# PWS.net
KiCad netlist of a schematic drawn in EAGLE
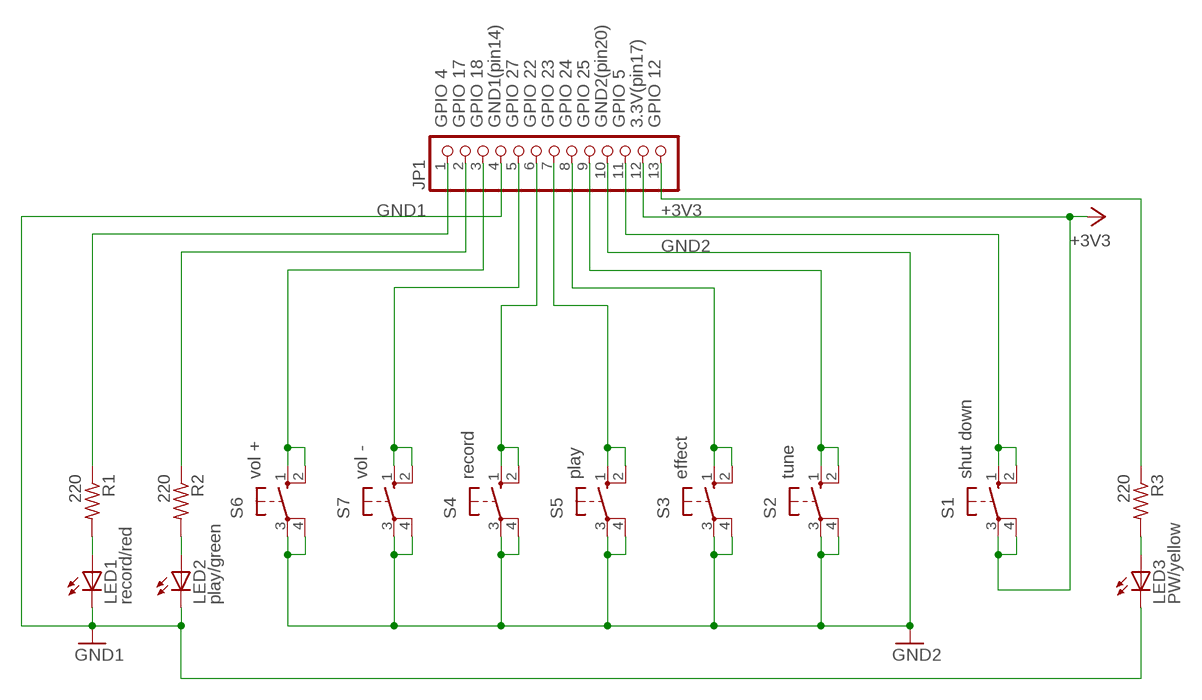
[diagram p0: schematic, sheet 1]

(export (version "E")
  (design (tool "Eeschema 10.0.6"))
  (components
    (comp (ref "JP1")
      (value "PINHD-1X13")
      (footprint "eagle-import:1X13")
      (libsource (lib "eagle-import") (part "PINHD-1X13"))
    )
    (comp (ref "LED1")
      (value "record/red")
      (footprint "eagle-import:LED3MM")
      (libsource (lib "eagle-import") (part "LED3MM"))
    )
    (comp (ref "LED2")
      (value "play/green")
      (footprint "eagle-import:LED3MM")
      (libsource (lib "eagle-import") (part "LED3MM"))
    )
    (comp (ref "LED3")
      (value "PW/yellow")
      (footprint "eagle-import:LED3MM")
      (libsource (lib "eagle-import") (part "LED3MM"))
    )
    (comp (ref "R1")
      (value "220")
      (footprint "eagle-import:0204_5")
      (libsource (lib "eagle-import") (part "R-US_0204/5"))
    )
    (comp (ref "R2")
      (value "220")
      (footprint "eagle-import:0204_5")
      (libsource (lib "eagle-import") (part "R-US_0204/5"))
    )
    (comp (ref "R3")
      (value "220")
      (footprint "eagle-import:0204_5")
      (libsource (lib "eagle-import") (part "R-US_0204/5"))
    )
    (comp (ref "S1")
      (value "shut down")
      (footprint "eagle-import:B3F-10XX")
      (fields (field (name "MPN") "B3F-1000"))
      (libsource (lib "eagle-import") (part "10-XX"))
    )
    (comp (ref "S2")
      (value "tune")
      (footprint "eagle-import:B3F-10XX")
      (fields (field (name "MPN") "B3F-1000"))
      (libsource (lib "eagle-import") (part "10-XX"))
    )
    (comp (ref "S3")
      (value "effect")
      (footprint "eagle-import:B3F-10XX")
      (fields (field (name "MPN") "B3F-1000"))
      (libsource (lib "eagle-import") (part "10-XX"))
    )
    (comp (ref "S4")
      (value "record")
      (footprint "eagle-import:B3F-10XX")
      (fields (field (name "MPN") "B3F-1000"))
      (libsource (lib "eagle-import") (part "10-XX"))
    )
    (comp (ref "S5")
      (value "play")
      (footprint "eagle-import:B3F-10XX")
      (fields (field (name "MPN") "B3F-1000"))
      (libsource (lib "eagle-import") (part "10-XX"))
    )
    (comp (ref "S6")
      (value "vol +")
      (footprint "eagle-import:B3F-10XX")
      (fields (field (name "MPN") "B3F-1000"))
      (libsource (lib "eagle-import") (part "10-XX"))
    )
    (comp (ref "S7")
      (value "vol -")
      (footprint "eagle-import:B3F-10XX")
      (fields (field (name "MPN") "B3F-1000"))
      (libsource (lib "eagle-import") (part "10-XX"))
    )
  )
  (nets
    (net (code "1") (name "+3V3") (class "Default")
      (node (ref "JP1") (pin "12") (pinfunction "12_12") (pintype "passive"))
      (node (ref "S1") (pin "3") (pinfunction "P_3") (pintype "passive"))
      (node (ref "S1") (pin "4") (pinfunction "P1_4") (pintype "passive"))
    )
    (net (code "2") (name "GND1") (class "Default")
      (node (ref "JP1") (pin "4") (pinfunction "4_4") (pintype "passive"))
      (node (ref "LED1") (pin "K") (pinfunction "C_K") (pintype "passive"))
      (node (ref "LED2") (pin "K") (pinfunction "C_K") (pintype "passive"))
      (node (ref "LED3") (pin "K") (pinfunction "C_K") (pintype "passive"))
    )
    (net (code "3") (name "GND2") (class "Default")
      (node (ref "JP1") (pin "10") (pinfunction "10_10") (pintype "passive"))
      (node (ref "S2") (pin "3") (pinfunction "P_3") (pintype "passive"))
      (node (ref "S2") (pin "4") (pinfunction "P1_4") (pintype "passive"))
      (node (ref "S3") (pin "3") (pinfunction "P_3") (pintype "passive"))
      (node (ref "S3") (pin "4") (pinfunction "P1_4") (pintype "passive"))
      (node (ref "S4") (pin "3") (pinfunction "P_3") (pintype "passive"))
      (node (ref "S4") (pin "4") (pinfunction "P1_4") (pintype "passive"))
      (node (ref "S5") (pin "3") (pinfunction "P_3") (pintype "passive"))
      (node (ref "S5") (pin "4") (pinfunction "P1_4") (pintype "passive"))
      (node (ref "S6") (pin "3") (pinfunction "P_3") (pintype "passive"))
      (node (ref "S6") (pin "4") (pinfunction "P1_4") (pintype "passive"))
      (node (ref "S7") (pin "3") (pinfunction "P_3") (pintype "passive"))
      (node (ref "S7") (pin "4") (pinfunction "P1_4") (pintype "passive"))
    )
    (net (code "4") (name "Net-(JP1-Pad1)") (class "Default")
      (node (ref "JP1") (pin "1") (pinfunction "1_1") (pintype "passive"))
      (node (ref "R1") (pin "1") (pinfunction "1_1") (pintype "passive"))
    )
    (net (code "5") (name "Net-(JP1-Pad2)") (class "Default")
      (node (ref "JP1") (pin "2") (pinfunction "2_2") (pintype "passive"))
      (node (ref "R2") (pin "1") (pinfunction "1_1") (pintype "passive"))
    )
    (net (code "6") (name "Net-(JP1-Pad13)") (class "Default")
      (node (ref "JP1") (pin "13") (pinfunction "13_13") (pintype "passive"))
      (node (ref "R3") (pin "1") (pinfunction "1_1") (pintype "passive"))
    )
    (net (code "7") (name "Net-(LED1-PadA)") (class "Default")
      (node (ref "LED1") (pin "A") (pinfunction "A_A") (pintype "passive"))
      (node (ref "R1") (pin "2") (pinfunction "2_2") (pintype "passive"))
    )
    (net (code "8") (name "Net-(LED2-PadA)") (class "Default")
      (node (ref "LED2") (pin "A") (pinfunction "A_A") (pintype "passive"))
      (node (ref "R2") (pin "2") (pinfunction "2_2") (pintype "passive"))
    )
    (net (code "9") (name "Net-(LED3-PadA)") (class "Default")
      (node (ref "LED3") (pin "A") (pinfunction "A_A") (pintype "passive"))
      (node (ref "R3") (pin "2") (pinfunction "2_2") (pintype "passive"))
    )
    (net (code "10") (name "Net-(S1-S)") (class "Default")
      (node (ref "JP1") (pin "11") (pinfunction "11_11") (pintype "passive"))
      (node (ref "S1") (pin "1") (pinfunction "S_1") (pintype "passive"))
      (node (ref "S1") (pin "2") (pinfunction "S1_2") (pintype "passive"))
    )
    (net (code "11") (name "Net-(S2-S)") (class "Default")
      (node (ref "JP1") (pin "9") (pinfunction "9_9") (pintype "passive"))
      (node (ref "S2") (pin "1") (pinfunction "S_1") (pintype "passive"))
      (node (ref "S2") (pin "2") (pinfunction "S1_2") (pintype "passive"))
    )
    (net (code "12") (name "Net-(S3-S)") (class "Default")
      (node (ref "JP1") (pin "8") (pinfunction "8_8") (pintype "passive"))
      (node (ref "S3") (pin "1") (pinfunction "S_1") (pintype "passive"))
      (node (ref "S3") (pin "2") (pinfunction "S1_2") (pintype "passive"))
    )
    (net (code "13") (name "Net-(S4-S)") (class "Default")
      (node (ref "JP1") (pin "6") (pinfunction "6_6") (pintype "passive"))
      (node (ref "S4") (pin "1") (pinfunction "S_1") (pintype "passive"))
      (node (ref "S4") (pin "2") (pinfunction "S1_2") (pintype "passive"))
    )
    (net (code "14") (name "Net-(S5-S)") (class "Default")
      (node (ref "JP1") (pin "7") (pinfunction "7_7") (pintype "passive"))
      (node (ref "S5") (pin "1") (pinfunction "S_1") (pintype "passive"))
      (node (ref "S5") (pin "2") (pinfunction "S1_2") (pintype "passive"))
    )
    (net (code "15") (name "Net-(S6-S)") (class "Default")
      (node (ref "JP1") (pin "3") (pinfunction "3_3") (pintype "passive"))
      (node (ref "S6") (pin "1") (pinfunction "S_1") (pintype "passive"))
      (node (ref "S6") (pin "2") (pinfunction "S1_2") (pintype "passive"))
    )
    (net (code "16") (name "Net-(S7-S)") (class "Default")
      (node (ref "JP1") (pin "5") (pinfunction "5_5") (pintype "passive"))
      (node (ref "S7") (pin "1") (pinfunction "S_1") (pintype "passive"))
      (node (ref "S7") (pin "2") (pinfunction "S1_2") (pintype "passive"))
    )
  )
)
